# pid_demo.net
KiCad netlist of a schematic drawn in EAGLE
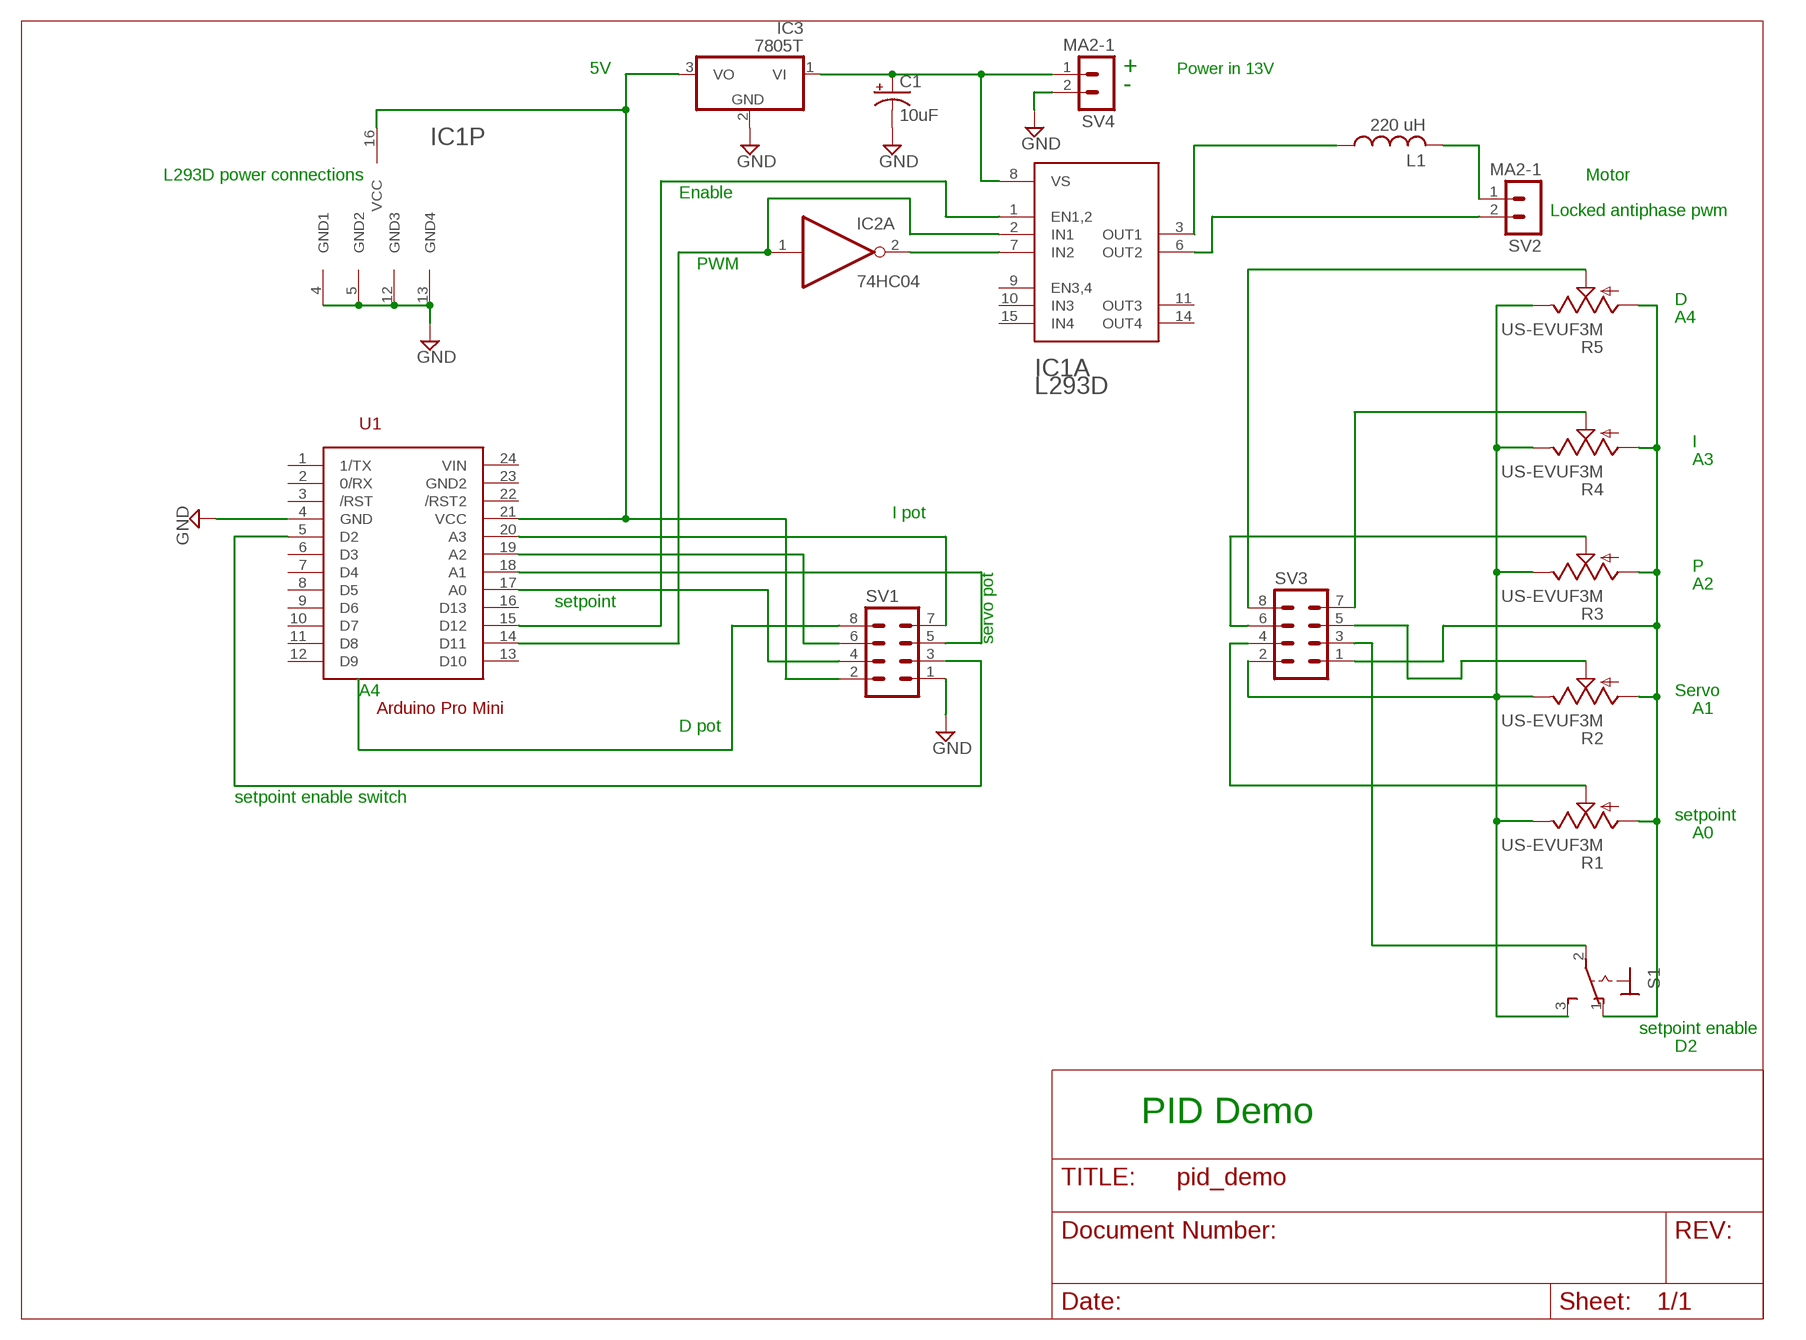
[diagram p0: schematic, sheet 1]

(export (version "E")
  (design (tool "Eeschema 10.0.6"))
  (components
    (comp (ref "C1")
      (value "10uF")
      (footprint "eagle-import:E5-5")
      (libsource (lib "eagle-import") (part "CPOL-USE5-5"))
    )
    (comp (ref "IC1")
      (value "L293D")
      (footprint "eagle-import:DIP16")
      (libsource (lib "eagle-import") (part "L293D"))
    )
    (comp (ref "IC2")
      (value "74HC04")
      (footprint "eagle-import:DIL14")
      (libsource (lib "eagle-import") (part "7404NALS"))
    )
    (comp (ref "IC3")
      (value "7805T")
      (footprint "eagle-import:TO220H")
      (libsource (lib "eagle-import") (part "78T05"))
    )
    (comp (ref "L1")
      (value "220 uH")
      (footprint "eagle-import:TJ4-U1")
      (libsource (lib "eagle-import") (part "L-USTJ4-U1"))
    )
    (comp (ref "R1")
      (value "US-EVUF3M")
      (footprint "eagle-import:EVUFXM")
      (libsource (lib "eagle-import") (part "US-EVUMF3"))
    )
    (comp (ref "R2")
      (value "US-EVUF3M")
      (footprint "eagle-import:EVUFXM")
      (libsource (lib "eagle-import") (part "US-EVUMF3"))
    )
    (comp (ref "R3")
      (value "US-EVUF3M")
      (footprint "eagle-import:EVUFXM")
      (libsource (lib "eagle-import") (part "US-EVUMF3"))
    )
    (comp (ref "R4")
      (value "US-EVUF3M")
      (footprint "eagle-import:EVUFXM")
      (libsource (lib "eagle-import") (part "US-EVUMF3"))
    )
    (comp (ref "R5")
      (value "US-EVUF3M")
      (footprint "eagle-import:EVUFXM")
      (libsource (lib "eagle-import") (part "US-EVUMF3"))
    )
    (comp (ref "S1")
      (value "320-916")
      (footprint "eagle-import:320-916")
      (libsource (lib "eagle-import") (part "320-916"))
    )
    (comp (ref "SV1")
      (value "MA04-2")
      (footprint "eagle-import:MA04-2")
      (libsource (lib "eagle-import") (part "MA04-2"))
    )
    (comp (ref "SV2")
      (value "MA2-1")
      (footprint "eagle-import:MA02-1")
      (libsource (lib "eagle-import") (part "MA2-1"))
    )
    (comp (ref "SV3")
      (value "MA04-2")
      (footprint "eagle-import:MA04-2")
      (libsource (lib "eagle-import") (part "MA04-2"))
    )
    (comp (ref "SV4")
      (value "MA2-1")
      (footprint "eagle-import:MA02-1")
      (libsource (lib "eagle-import") (part "MA2-1"))
    )
    (comp (ref "U1")
      (value "Arduino Pro Mini")
      (footprint "eagle-import:DIL24")
      (libsource (lib "eagle-import") (part "ARDUINO_PRO_MINI"))
    )
  )
  (nets
    (net (code "1") (name "GND") (class "Default")
      (node (ref "C1") (pin "-") (pinfunction "-_-") (pintype "passive"))
      (node (ref "IC1") (pin "12") (pinfunction "GND3_12") (pintype "power_in"))
      (node (ref "IC1") (pin "13") (pinfunction "GND4_13") (pintype "power_in"))
      (node (ref "IC1") (pin "4") (pinfunction "GND1_4") (pintype "power_in"))
      (node (ref "IC1") (pin "5") (pinfunction "GND2_5") (pintype "power_in"))
      (node (ref "IC3") (pin "2") (pinfunction "GND_2") (pintype "passive"))
      (node (ref "SV1") (pin "1") (pinfunction "1_1") (pintype "passive"))
      (node (ref "SV4") (pin "2") (pinfunction "2_2") (pintype "passive"))
      (node (ref "U1") (pin "4") (pinfunction "GND_4") (pintype "bidirectional"))
    )
    (net (code "2") (name "Net-(IC1A-EN1,2)") (class "Default")
      (node (ref "IC1") (pin "1") (pinfunction "EN1,2_1") (pintype "input"))
      (node (ref "U1") (pin "15") (pinfunction "D12_15") (pintype "bidirectional"))
    )
    (net (code "3") (name "Net-(IC1A-IN1)") (class "Default")
      (node (ref "IC1") (pin "2") (pinfunction "IN1_2") (pintype "input"))
      (node (ref "IC2") (pin "1") (pinfunction "I_1") (pintype "input"))
      (node (ref "U1") (pin "14") (pinfunction "D11_14") (pintype "bidirectional"))
    )
    (net (code "4") (name "Net-(IC1A-IN2)") (class "Default")
      (node (ref "IC1") (pin "7") (pinfunction "IN2_7") (pintype "input"))
      (node (ref "IC2") (pin "2") (pinfunction "O_2") (pintype "output"))
    )
    (net (code "5") (name "Net-(IC1A-OUT1)") (class "Default")
      (node (ref "IC1") (pin "3") (pinfunction "OUT1_3") (pintype "output"))
      (node (ref "L1") (pin "1") (pinfunction "1_1") (pintype "passive"))
    )
    (net (code "6") (name "Net-(IC1A-OUT2)") (class "Default")
      (node (ref "IC1") (pin "6") (pinfunction "OUT2_6") (pintype "output"))
      (node (ref "SV2") (pin "2") (pinfunction "2_2") (pintype "passive"))
    )
    (net (code "7") (name "Net-(IC1A-VS)") (class "Default")
      (node (ref "C1") (pin "+") (pinfunction "+_+") (pintype "passive"))
      (node (ref "IC1") (pin "8") (pinfunction "VS_8") (pintype "power_in"))
      (node (ref "IC3") (pin "1") (pinfunction "VI_1") (pintype "input"))
      (node (ref "SV4") (pin "1") (pinfunction "1_1") (pintype "passive"))
    )
    (net (code "8") (name "Net-(IC1B-VCC)") (class "Default")
      (node (ref "IC1") (pin "16") (pinfunction "VCC_16") (pintype "power_in"))
      (node (ref "IC3") (pin "3") (pinfunction "VO_3") (pintype "passive"))
      (node (ref "SV1") (pin "2") (pinfunction "2_2") (pintype "passive"))
      (node (ref "U1") (pin "21") (pinfunction "VCC_21") (pintype "bidirectional"))
    )
    (net (code "9") (name "Net-(L1-Pad2)") (class "Default")
      (node (ref "L1") (pin "2") (pinfunction "2_2") (pintype "passive"))
      (node (ref "SV2") (pin "1") (pinfunction "1_1") (pintype "passive"))
    )
    (net (code "10") (name "Net-(R1-A)") (class "Default")
      (node (ref "R1") (pin "1") (pinfunction "A_1") (pintype "passive"))
      (node (ref "R2") (pin "1") (pinfunction "A_1") (pintype "passive"))
      (node (ref "R3") (pin "1") (pinfunction "A_1") (pintype "passive"))
      (node (ref "R4") (pin "1") (pinfunction "A_1") (pintype "passive"))
      (node (ref "R5") (pin "1") (pinfunction "A_1") (pintype "passive"))
      (node (ref "S1") (pin "1") (pinfunction "O_1") (pintype "passive"))
      (node (ref "SV3") (pin "1") (pinfunction "1_1") (pintype "passive"))
    )
    (net (code "11") (name "Net-(R1-E)") (class "Default")
      (node (ref "R1") (pin "3") (pinfunction "E_3") (pintype "passive"))
      (node (ref "R2") (pin "3") (pinfunction "E_3") (pintype "passive"))
      (node (ref "R3") (pin "3") (pinfunction "E_3") (pintype "passive"))
      (node (ref "R4") (pin "3") (pinfunction "E_3") (pintype "passive"))
      (node (ref "R5") (pin "3") (pinfunction "E_3") (pintype "passive"))
      (node (ref "S1") (pin "3") (pinfunction "S_3") (pintype "passive"))
      (node (ref "SV3") (pin "2") (pinfunction "2_2") (pintype "passive"))
    )
    (net (code "12") (name "Net-(R1-S)") (class "Default")
      (node (ref "R1") (pin "2") (pinfunction "S_2") (pintype "passive"))
      (node (ref "SV3") (pin "4") (pinfunction "4_4") (pintype "passive"))
    )
    (net (code "13") (name "Net-(R2-S)") (class "Default")
      (node (ref "R2") (pin "2") (pinfunction "S_2") (pintype "passive"))
      (node (ref "SV3") (pin "5") (pinfunction "5_5") (pintype "passive"))
    )
    (net (code "14") (name "Net-(R3-S)") (class "Default")
      (node (ref "R3") (pin "2") (pinfunction "S_2") (pintype "passive"))
      (node (ref "SV3") (pin "6") (pinfunction "6_6") (pintype "passive"))
    )
    (net (code "15") (name "Net-(R4-S)") (class "Default")
      (node (ref "R4") (pin "2") (pinfunction "S_2") (pintype "passive"))
      (node (ref "SV3") (pin "7") (pinfunction "7_7") (pintype "passive"))
    )
    (net (code "16") (name "Net-(R5-S)") (class "Default")
      (node (ref "R5") (pin "2") (pinfunction "S_2") (pintype "passive"))
      (node (ref "SV3") (pin "8") (pinfunction "8_8") (pintype "passive"))
    )
    (net (code "17") (name "Net-(S1-P)") (class "Default")
      (node (ref "S1") (pin "2") (pinfunction "P_2") (pintype "passive"))
      (node (ref "SV3") (pin "3") (pinfunction "3_3") (pintype "passive"))
    )
    (net (code "18") (name "Net-(U1-A0)") (class "Default")
      (node (ref "SV1") (pin "4") (pinfunction "4_4") (pintype "passive"))
      (node (ref "U1") (pin "17") (pinfunction "A0_17") (pintype "bidirectional"))
    )
    (net (code "19") (name "Net-(U1-A1)") (class "Default")
      (node (ref "SV1") (pin "5") (pinfunction "5_5") (pintype "passive"))
      (node (ref "U1") (pin "18") (pinfunction "A1_18") (pintype "bidirectional"))
    )
    (net (code "20") (name "Net-(U1-A2)") (class "Default")
      (node (ref "SV1") (pin "6") (pinfunction "6_6") (pintype "passive"))
      (node (ref "U1") (pin "19") (pinfunction "A2_19") (pintype "bidirectional"))
    )
    (net (code "21") (name "Net-(U1-A3)") (class "Default")
      (node (ref "SV1") (pin "7") (pinfunction "7_7") (pintype "passive"))
      (node (ref "U1") (pin "20") (pinfunction "A3_20") (pintype "bidirectional"))
    )
    (net (code "22") (name "Net-(U1-D2)") (class "Default")
      (node (ref "SV1") (pin "3") (pinfunction "3_3") (pintype "passive"))
      (node (ref "U1") (pin "5") (pinfunction "D2_5") (pintype "bidirectional"))
    )
    (net (code "23") (name "unconnected-(IC1A-EN3,4-Pad9)") (class "Default")
      (node (ref "IC1") (pin "9") (pinfunction "EN3,4_9") (pintype "input"))
    )
    (net (code "24") (name "unconnected-(IC1A-IN3-Pad10)") (class "Default")
      (node (ref "IC1") (pin "10") (pinfunction "IN3_10") (pintype "input"))
    )
    (net (code "25") (name "unconnected-(IC1A-IN4-Pad15)") (class "Default")
      (node (ref "IC1") (pin "15") (pinfunction "IN4_15") (pintype "input"))
    )
    (net (code "26") (name "unconnected-(IC1A-OUT3-Pad11)") (class "Default")
      (node (ref "IC1") (pin "11") (pinfunction "OUT3_11") (pintype "output"))
    )
    (net (code "27") (name "unconnected-(IC1A-OUT4-Pad14)") (class "Default")
      (node (ref "IC1") (pin "14") (pinfunction "OUT4_14") (pintype "output"))
    )
    (net (code "28") (name "unconnected-(SV1-Pad8)") (class "Default")
      (node (ref "SV1") (pin "8") (pinfunction "8_8") (pintype "passive"))
    )
    (net (code "29") (name "unconnected-(U1-0{slash}RX-Pad2)") (class "Default")
      (node (ref "U1") (pin "2") (pinfunction "0/RX_2") (pintype "bidirectional"))
    )
    (net (code "30") (name "unconnected-(U1-1{slash}TX-Pad1)") (class "Default")
      (node (ref "U1") (pin "1") (pinfunction "1/TX_1") (pintype "bidirectional"))
    )
    (net (code "31") (name "unconnected-(U1-D3-Pad6)") (class "Default")
      (node (ref "U1") (pin "6") (pinfunction "D3_6") (pintype "bidirectional"))
    )
    (net (code "32") (name "unconnected-(U1-D4-Pad7)") (class "Default")
      (node (ref "U1") (pin "7") (pinfunction "D4_7") (pintype "bidirectional"))
    )
    (net (code "33") (name "unconnected-(U1-D5-Pad8)") (class "Default")
      (node (ref "U1") (pin "8") (pinfunction "D5_8") (pintype "bidirectional"))
    )
    (net (code "34") (name "unconnected-(U1-D6-Pad9)") (class "Default")
      (node (ref "U1") (pin "9") (pinfunction "D6_9") (pintype "bidirectional"))
    )
    (net (code "35") (name "unconnected-(U1-D7-Pad10)") (class "Default")
      (node (ref "U1") (pin "10") (pinfunction "D7_10") (pintype "bidirectional"))
    )
    (net (code "36") (name "unconnected-(U1-D8-Pad11)") (class "Default")
      (node (ref "U1") (pin "11") (pinfunction "D8_11") (pintype "bidirectional"))
    )
    (net (code "37") (name "unconnected-(U1-D9-Pad12)") (class "Default")
      (node (ref "U1") (pin "12") (pinfunction "D9_12") (pintype "bidirectional"))
    )
    (net (code "38") (name "unconnected-(U1-D10-Pad13)") (class "Default")
      (node (ref "U1") (pin "13") (pinfunction "D10_13") (pintype "bidirectional"))
    )
    (net (code "39") (name "unconnected-(U1-D13-Pad16)") (class "Default")
      (node (ref "U1") (pin "16") (pinfunction "D13_16") (pintype "bidirectional"))
    )
    (net (code "40") (name "unconnected-(U1-GND2-Pad23)") (class "Default")
      (node (ref "U1") (pin "23") (pinfunction "GND2_23") (pintype "bidirectional"))
    )
    (net (code "41") (name "unconnected-(U1-VIN-Pad24)") (class "Default")
      (node (ref "U1") (pin "24") (pinfunction "VIN_24") (pintype "bidirectional"))
    )
    (net (code "42") (name "unconnected-(U1-{slash}RST-Pad3)") (class "Default")
      (node (ref "U1") (pin "3") (pinfunction "/RST_3") (pintype "bidirectional"))
    )
    (net (code "43") (name "unconnected-(U1-{slash}RST2-Pad22)") (class "Default")
      (node (ref "U1") (pin "22") (pinfunction "/RST2_22") (pintype "bidirectional"))
    )
  )
)
